# main.net
KiCad netlist of a schematic drawn in EAGLE
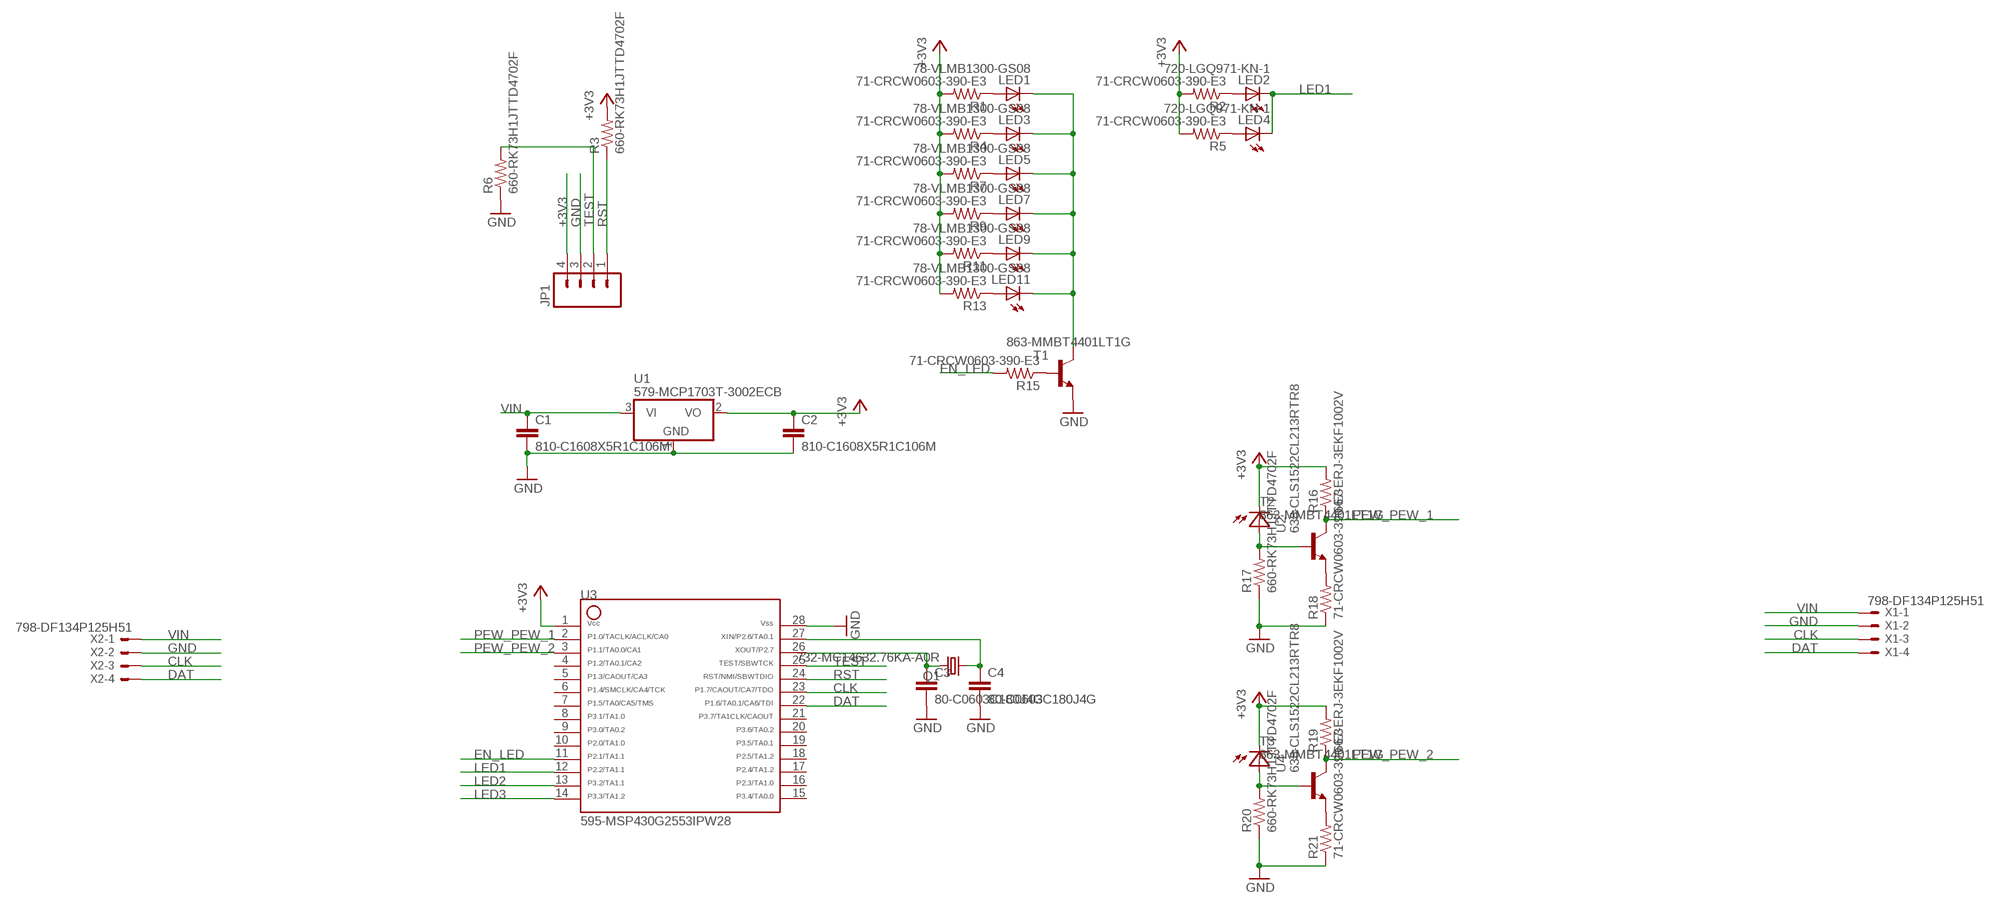
[diagram p0: schematic, sheet 1]

(export (version "E")
  (design (tool "Eeschema 10.0.6"))
  (components
    (comp (ref "C1")
      (value "810-C1608X5R1C106M")
      (footprint "eagle-import:0603-CAP")
      (libsource (lib "eagle-import") (part "CAP0603-CAP"))
    )
    (comp (ref "C2")
      (value "810-C1608X5R1C106M")
      (footprint "eagle-import:0603-CAP")
      (libsource (lib "eagle-import") (part "CAP0603-CAP"))
    )
    (comp (ref "C3")
      (value "80-C0603C180J4G")
      (footprint "eagle-import:0603-CAP")
      (libsource (lib "eagle-import") (part "CAP0603-CAP"))
    )
    (comp (ref "C4")
      (value "80-C0603C180J4G")
      (footprint "eagle-import:0603-CAP")
      (libsource (lib "eagle-import") (part "CAP0603-CAP"))
    )
    (comp (ref "JP1")
      (value "M04PTH")
      (footprint "eagle-import:1X04")
      (libsource (lib "eagle-import") (part "M04PTH"))
    )
    (comp (ref "LED1")
      (value "78-VLMB1300-GS08")
      (footprint "eagle-import:LED-0603")
      (libsource (lib "eagle-import") (part "LED0603"))
    )
    (comp (ref "LED2")
      (value "720-LGQ971-KN-1")
      (footprint "eagle-import:LED-0603")
      (libsource (lib "eagle-import") (part "LED0603"))
    )
    (comp (ref "LED3")
      (value "78-VLMB1300-GS08")
      (footprint "eagle-import:LED-0603")
      (libsource (lib "eagle-import") (part "LED0603"))
    )
    (comp (ref "LED4")
      (value "720-LGQ971-KN-1")
      (footprint "eagle-import:LED-0603")
      (libsource (lib "eagle-import") (part "LED0603"))
    )
    (comp (ref "LED5")
      (value "78-VLMB1300-GS08")
      (footprint "eagle-import:LED-0603")
      (libsource (lib "eagle-import") (part "LED0603"))
    )
    (comp (ref "LED7")
      (value "78-VLMB1300-GS08")
      (footprint "eagle-import:LED-0603")
      (libsource (lib "eagle-import") (part "LED0603"))
    )
    (comp (ref "LED9")
      (value "78-VLMB1300-GS08")
      (footprint "eagle-import:LED-0603")
      (libsource (lib "eagle-import") (part "LED0603"))
    )
    (comp (ref "LED11")
      (value "78-VLMB1300-GS08")
      (footprint "eagle-import:LED-0603")
      (libsource (lib "eagle-import") (part "LED0603"))
    )
    (comp (ref "Q1")
      (value "732-MC14632.76KA-A0R")
      (footprint "eagle-import:CRYSTAL-32KHZ-SMD_EPSON_MC146")
      (libsource (lib "eagle-import") (part "CRYSTALEPSONMC146"))
    )
    (comp (ref "R1")
      (value "71-CRCW0603-390-E3")
      (footprint "eagle-import:R0603")
      (libsource (lib "eagle-import") (part "R-US_R0603"))
    )
    (comp (ref "R2")
      (value "71-CRCW0603-390-E3")
      (footprint "eagle-import:R0603")
      (libsource (lib "eagle-import") (part "R-US_R0603"))
    )
    (comp (ref "R3")
      (value "660-RK73H1JTTD4702F")
      (footprint "eagle-import:R0603")
      (libsource (lib "eagle-import") (part "R-US_R0603"))
    )
    (comp (ref "R4")
      (value "71-CRCW0603-390-E3")
      (footprint "eagle-import:R0603")
      (libsource (lib "eagle-import") (part "R-US_R0603"))
    )
    (comp (ref "R5")
      (value "71-CRCW0603-390-E3")
      (footprint "eagle-import:R0603")
      (libsource (lib "eagle-import") (part "R-US_R0603"))
    )
    (comp (ref "R6")
      (value "660-RK73H1JTTD4702F")
      (footprint "eagle-import:R0603")
      (libsource (lib "eagle-import") (part "R-US_R0603"))
    )
    (comp (ref "R7")
      (value "71-CRCW0603-390-E3")
      (footprint "eagle-import:R0603")
      (libsource (lib "eagle-import") (part "R-US_R0603"))
    )
    (comp (ref "R9")
      (value "71-CRCW0603-390-E3")
      (footprint "eagle-import:R0603")
      (libsource (lib "eagle-import") (part "R-US_R0603"))
    )
    (comp (ref "R11")
      (value "71-CRCW0603-390-E3")
      (footprint "eagle-import:R0603")
      (libsource (lib "eagle-import") (part "R-US_R0603"))
    )
    (comp (ref "R13")
      (value "71-CRCW0603-390-E3")
      (footprint "eagle-import:R0603")
      (libsource (lib "eagle-import") (part "R-US_R0603"))
    )
    (comp (ref "R15")
      (value "71-CRCW0603-390-E3")
      (footprint "eagle-import:R0603")
      (libsource (lib "eagle-import") (part "R-US_R0603"))
    )
    (comp (ref "R16")
      (value "667-ERJ-3EKF1002V")
      (footprint "eagle-import:R0603")
      (libsource (lib "eagle-import") (part "R-US_R0603"))
    )
    (comp (ref "R17")
      (value "660-RK73H1JTTD4702F")
      (footprint "eagle-import:R0603")
      (libsource (lib "eagle-import") (part "R-US_R0603"))
    )
    (comp (ref "R18")
      (value "71-CRCW0603-390-E3")
      (footprint "eagle-import:R0603")
      (libsource (lib "eagle-import") (part "R-US_R0603"))
    )
    (comp (ref "R19")
      (value "667-ERJ-3EKF1002V")
      (footprint "eagle-import:R0603")
      (libsource (lib "eagle-import") (part "R-US_R0603"))
    )
    (comp (ref "R20")
      (value "660-RK73H1JTTD4702F")
      (footprint "eagle-import:R0603")
      (libsource (lib "eagle-import") (part "R-US_R0603"))
    )
    (comp (ref "R21")
      (value "71-CRCW0603-390-E3")
      (footprint "eagle-import:R0603")
      (libsource (lib "eagle-import") (part "R-US_R0603"))
    )
    (comp (ref "T1")
      (value "863-MMBT4401LT1G")
      (footprint "eagle-import:SOT23-BEC")
      (libsource (lib "eagle-import") (part "-NPN-SOT23-BECMMBT4401LT1"))
    )
    (comp (ref "T2")
      (value "863-MMBT4401LT1G")
      (footprint "eagle-import:SOT23-BEC")
      (libsource (lib "eagle-import") (part "-NPN-SOT23-BECMMBT4401LT1"))
    )
    (comp (ref "T3")
      (value "863-MMBT4401LT1G")
      (footprint "eagle-import:SOT23-BEC")
      (libsource (lib "eagle-import") (part "-NPN-SOT23-BECMMBT4401LT1"))
    )
    (comp (ref "U1")
      (value "579-MCP1703T-3002ECB")
      (footprint "eagle-import:SOT23")
      (libsource (lib "eagle-import") (part "MCP1703CB"))
    )
    (comp (ref "U2")
      (value "638-CLS1522CL213RTR8")
      (footprint "eagle-import:CLS15")
      (libsource (lib "eagle-import") (part "CLS15CLS15"))
    )
    (comp (ref "U3")
      (value "595-MSP430G2553IPW28")
      (footprint "eagle-import:PW28")
      (libsource (lib "eagle-import") (part "MSP430G2553"))
    )
    (comp (ref "U4")
      (value "638-CLS1522CL213RTR8")
      (footprint "eagle-import:CLS15")
      (libsource (lib "eagle-import") (part "CLS15CLS15"))
    )
    (comp (ref "X1")
      (value "798-DF134P125H51")
      (footprint "eagle-import:53261-04")
      (libsource (lib "eagle-import") (part "53?-04261"))
    )
    (comp (ref "X2")
      (value "798-DF134P125H51")
      (footprint "eagle-import:53261-04")
      (libsource (lib "eagle-import") (part "53?-04261"))
    )
  )
  (nets
    (net (code "1") (name "+3V3") (class "Default")
      (node (ref "C2") (pin "1") (pinfunction "1_1") (pintype "passive"))
      (node (ref "JP1") (pin "4") (pinfunction "4_4") (pintype "passive"))
      (node (ref "R1") (pin "2") (pinfunction "2_2") (pintype "passive"))
      (node (ref "R11") (pin "2") (pinfunction "2_2") (pintype "passive"))
      (node (ref "R13") (pin "2") (pinfunction "2_2") (pintype "passive"))
      (node (ref "R16") (pin "2") (pinfunction "2_2") (pintype "passive"))
      (node (ref "R19") (pin "2") (pinfunction "2_2") (pintype "passive"))
      (node (ref "R2") (pin "2") (pinfunction "2_2") (pintype "passive"))
      (node (ref "R3") (pin "2") (pinfunction "2_2") (pintype "passive"))
      (node (ref "R4") (pin "2") (pinfunction "2_2") (pintype "passive"))
      (node (ref "R5") (pin "2") (pinfunction "2_2") (pintype "passive"))
      (node (ref "R7") (pin "2") (pinfunction "2_2") (pintype "passive"))
      (node (ref "R9") (pin "2") (pinfunction "2_2") (pintype "passive"))
      (node (ref "U1") (pin "2") (pinfunction "VO_2") (pintype "passive"))
      (node (ref "U2") (pin "3") (pinfunction "C_3") (pintype "passive"))
      (node (ref "U2") (pin "4") (pinfunction "C_4") (pintype "passive"))
      (node (ref "U3") (pin "1") (pinfunction "1_1") (pintype "power_in"))
      (node (ref "U4") (pin "3") (pinfunction "C_3") (pintype "passive"))
      (node (ref "U4") (pin "4") (pinfunction "C_4") (pintype "passive"))
    )
    (net (code "2") (name "/CLK") (class "Default")
      (node (ref "U3") (pin "23") (pinfunction "23_23") (pintype "bidirectional"))
      (node (ref "X1") (pin "3") (pinfunction "S_3") (pintype "passive"))
      (node (ref "X2") (pin "3") (pinfunction "S_3") (pintype "passive"))
    )
    (net (code "3") (name "/DAT") (class "Default")
      (node (ref "U3") (pin "22") (pinfunction "22_22") (pintype "bidirectional"))
      (node (ref "X1") (pin "4") (pinfunction "S_4") (pintype "passive"))
      (node (ref "X2") (pin "4") (pinfunction "S_4") (pintype "passive"))
    )
    (net (code "4") (name "/EN_LED") (class "Default")
      (node (ref "R15") (pin "2") (pinfunction "2_2") (pintype "passive"))
      (node (ref "U3") (pin "11") (pinfunction "11_11") (pintype "bidirectional"))
    )
    (net (code "5") (name "/LED1") (class "Default")
      (node (ref "LED2") (pin "C") (pinfunction "C_C") (pintype "passive"))
      (node (ref "LED4") (pin "C") (pinfunction "C_C") (pintype "passive"))
      (node (ref "U3") (pin "12") (pinfunction "12_12") (pintype "bidirectional"))
    )
    (net (code "6") (name "/LED2") (class "Default")
      (node (ref "U3") (pin "13") (pinfunction "13_13") (pintype "bidirectional"))
    )
    (net (code "7") (name "/LED3") (class "Default")
      (node (ref "U3") (pin "14") (pinfunction "14_14") (pintype "bidirectional"))
    )
    (net (code "8") (name "/PEW_PEW_1") (class "Default")
      (node (ref "R16") (pin "1") (pinfunction "1_1") (pintype "passive"))
      (node (ref "T2") (pin "C") (pinfunction "C_C") (pintype "passive"))
      (node (ref "U3") (pin "2") (pinfunction "2_2") (pintype "bidirectional"))
    )
    (net (code "9") (name "/PEW_PEW_2") (class "Default")
      (node (ref "R19") (pin "1") (pinfunction "1_1") (pintype "passive"))
      (node (ref "T3") (pin "C") (pinfunction "C_C") (pintype "passive"))
      (node (ref "U3") (pin "3") (pinfunction "3_3") (pintype "bidirectional"))
    )
    (net (code "10") (name "/RST") (class "Default")
      (node (ref "JP1") (pin "1") (pinfunction "1_1") (pintype "passive"))
      (node (ref "R3") (pin "1") (pinfunction "1_1") (pintype "passive"))
      (node (ref "U3") (pin "24") (pinfunction "24_24") (pintype "bidirectional"))
    )
    (net (code "11") (name "/TEST") (class "Default")
      (node (ref "JP1") (pin "2") (pinfunction "2_2") (pintype "passive"))
      (node (ref "R6") (pin "2") (pinfunction "2_2") (pintype "passive"))
      (node (ref "U3") (pin "25") (pinfunction "25_25") (pintype "input"))
    )
    (net (code "12") (name "/VIN") (class "Default")
      (node (ref "C1") (pin "1") (pinfunction "1_1") (pintype "passive"))
      (node (ref "U1") (pin "3") (pinfunction "VI_3") (pintype "input"))
      (node (ref "X1") (pin "1") (pinfunction "S_1") (pintype "passive"))
      (node (ref "X2") (pin "1") (pinfunction "S_1") (pintype "passive"))
    )
    (net (code "13") (name "GND") (class "Default")
      (node (ref "C1") (pin "2") (pinfunction "2_2") (pintype "passive"))
      (node (ref "C2") (pin "2") (pinfunction "2_2") (pintype "passive"))
      (node (ref "C3") (pin "2") (pinfunction "2_2") (pintype "passive"))
      (node (ref "C4") (pin "2") (pinfunction "2_2") (pintype "passive"))
      (node (ref "JP1") (pin "3") (pinfunction "3_3") (pintype "passive"))
      (node (ref "R17") (pin "1") (pinfunction "1_1") (pintype "passive"))
      (node (ref "R18") (pin "1") (pinfunction "1_1") (pintype "passive"))
      (node (ref "R20") (pin "1") (pinfunction "1_1") (pintype "passive"))
      (node (ref "R21") (pin "1") (pinfunction "1_1") (pintype "passive"))
      (node (ref "R6") (pin "1") (pinfunction "1_1") (pintype "passive"))
      (node (ref "T1") (pin "E") (pinfunction "E_E") (pintype "passive"))
      (node (ref "U1") (pin "1") (pinfunction "GND_1") (pintype "passive"))
      (node (ref "U3") (pin "28") (pinfunction "28_28") (pintype "power_in"))
      (node (ref "X1") (pin "2") (pinfunction "S_2") (pintype "passive"))
      (node (ref "X2") (pin "2") (pinfunction "S_2") (pintype "passive"))
    )
    (net (code "14") (name "Net-(LED1-PadA)") (class "Default")
      (node (ref "LED1") (pin "A") (pinfunction "A_A") (pintype "passive"))
      (node (ref "R1") (pin "1") (pinfunction "1_1") (pintype "passive"))
    )
    (net (code "15") (name "Net-(LED1-PadC)") (class "Default")
      (node (ref "LED1") (pin "C") (pinfunction "C_C") (pintype "passive"))
      (node (ref "LED11") (pin "C") (pinfunction "C_C") (pintype "passive"))
      (node (ref "LED3") (pin "C") (pinfunction "C_C") (pintype "passive"))
      (node (ref "LED5") (pin "C") (pinfunction "C_C") (pintype "passive"))
      (node (ref "LED7") (pin "C") (pinfunction "C_C") (pintype "passive"))
      (node (ref "LED9") (pin "C") (pinfunction "C_C") (pintype "passive"))
      (node (ref "T1") (pin "C") (pinfunction "C_C") (pintype "passive"))
    )
    (net (code "16") (name "Net-(LED2-PadA)") (class "Default")
      (node (ref "LED2") (pin "A") (pinfunction "A_A") (pintype "passive"))
      (node (ref "R2") (pin "1") (pinfunction "1_1") (pintype "passive"))
    )
    (net (code "17") (name "Net-(LED3-PadA)") (class "Default")
      (node (ref "LED3") (pin "A") (pinfunction "A_A") (pintype "passive"))
      (node (ref "R4") (pin "1") (pinfunction "1_1") (pintype "passive"))
    )
    (net (code "18") (name "Net-(LED4-PadA)") (class "Default")
      (node (ref "LED4") (pin "A") (pinfunction "A_A") (pintype "passive"))
      (node (ref "R5") (pin "1") (pinfunction "1_1") (pintype "passive"))
    )
    (net (code "19") (name "Net-(LED5-PadA)") (class "Default")
      (node (ref "LED5") (pin "A") (pinfunction "A_A") (pintype "passive"))
      (node (ref "R7") (pin "1") (pinfunction "1_1") (pintype "passive"))
    )
    (net (code "20") (name "Net-(LED7-PadA)") (class "Default")
      (node (ref "LED7") (pin "A") (pinfunction "A_A") (pintype "passive"))
      (node (ref "R9") (pin "1") (pinfunction "1_1") (pintype "passive"))
    )
    (net (code "21") (name "Net-(LED9-PadA)") (class "Default")
      (node (ref "LED9") (pin "A") (pinfunction "A_A") (pintype "passive"))
      (node (ref "R11") (pin "1") (pinfunction "1_1") (pintype "passive"))
    )
    (net (code "22") (name "Net-(LED11-PadA)") (class "Default")
      (node (ref "LED11") (pin "A") (pinfunction "A_A") (pintype "passive"))
      (node (ref "R13") (pin "1") (pinfunction "1_1") (pintype "passive"))
    )
    (net (code "23") (name "Net-(Q1-1)") (class "Default")
      (node (ref "C4") (pin "1") (pinfunction "1_1") (pintype "passive"))
      (node (ref "Q1") (pin "P$2") (pinfunction "1_P$2") (pintype "passive"))
      (node (ref "U3") (pin "27") (pinfunction "27_27") (pintype "bidirectional"))
    )
    (net (code "24") (name "Net-(Q1-2)") (class "Default")
      (node (ref "C3") (pin "1") (pinfunction "1_1") (pintype "passive"))
      (node (ref "Q1") (pin "P$1") (pinfunction "2_P$1") (pintype "passive"))
      (node (ref "U3") (pin "26") (pinfunction "26_26") (pintype "bidirectional"))
    )
    (net (code "25") (name "Net-(R15-Pad1)") (class "Default")
      (node (ref "R15") (pin "1") (pinfunction "1_1") (pintype "passive"))
      (node (ref "T1") (pin "B") (pinfunction "B_B") (pintype "passive"))
    )
    (net (code "26") (name "Net-(R17-Pad2)") (class "Default")
      (node (ref "R17") (pin "2") (pinfunction "2_2") (pintype "passive"))
      (node (ref "T2") (pin "B") (pinfunction "B_B") (pintype "passive"))
      (node (ref "U2") (pin "1") (pinfunction "A_1") (pintype "passive"))
      (node (ref "U2") (pin "2") (pinfunction "A_2") (pintype "passive"))
    )
    (net (code "27") (name "Net-(R18-Pad2)") (class "Default")
      (node (ref "R18") (pin "2") (pinfunction "2_2") (pintype "passive"))
      (node (ref "T2") (pin "E") (pinfunction "E_E") (pintype "passive"))
    )
    (net (code "28") (name "Net-(R20-Pad2)") (class "Default")
      (node (ref "R20") (pin "2") (pinfunction "2_2") (pintype "passive"))
      (node (ref "T3") (pin "B") (pinfunction "B_B") (pintype "passive"))
      (node (ref "U4") (pin "1") (pinfunction "A_1") (pintype "passive"))
      (node (ref "U4") (pin "2") (pinfunction "A_2") (pintype "passive"))
    )
    (net (code "29") (name "Net-(R21-Pad2)") (class "Default")
      (node (ref "R21") (pin "2") (pinfunction "2_2") (pintype "passive"))
      (node (ref "T3") (pin "E") (pinfunction "E_E") (pintype "passive"))
    )
    (net (code "30") (name "unconnected-(U3-Pad4)") (class "Default")
      (node (ref "U3") (pin "4") (pinfunction "4_4") (pintype "bidirectional"))
    )
    (net (code "31") (name "unconnected-(U3-Pad5)") (class "Default")
      (node (ref "U3") (pin "5") (pinfunction "5_5") (pintype "bidirectional"))
    )
    (net (code "32") (name "unconnected-(U3-Pad6)") (class "Default")
      (node (ref "U3") (pin "6") (pinfunction "6_6") (pintype "bidirectional"))
    )
    (net (code "33") (name "unconnected-(U3-Pad7)") (class "Default")
      (node (ref "U3") (pin "7") (pinfunction "7_7") (pintype "bidirectional"))
    )
    (net (code "34") (name "unconnected-(U3-Pad8)") (class "Default")
      (node (ref "U3") (pin "8") (pinfunction "8_8") (pintype "bidirectional"))
    )
    (net (code "35") (name "unconnected-(U3-Pad9)") (class "Default")
      (node (ref "U3") (pin "9") (pinfunction "9_9") (pintype "bidirectional"))
    )
    (net (code "36") (name "unconnected-(U3-Pad10)") (class "Default")
      (node (ref "U3") (pin "10") (pinfunction "10_10") (pintype "bidirectional"))
    )
    (net (code "37") (name "unconnected-(U3-Pad15)") (class "Default")
      (node (ref "U3") (pin "15") (pinfunction "15_15") (pintype "bidirectional"))
    )
    (net (code "38") (name "unconnected-(U3-Pad16)") (class "Default")
      (node (ref "U3") (pin "16") (pinfunction "16_16") (pintype "bidirectional"))
    )
    (net (code "39") (name "unconnected-(U3-Pad17)") (class "Default")
      (node (ref "U3") (pin "17") (pinfunction "17_17") (pintype "bidirectional"))
    )
    (net (code "40") (name "unconnected-(U3-Pad18)") (class "Default")
      (node (ref "U3") (pin "18") (pinfunction "18_18") (pintype "bidirectional"))
    )
    (net (code "41") (name "unconnected-(U3-Pad19)") (class "Default")
      (node (ref "U3") (pin "19") (pinfunction "19_19") (pintype "bidirectional"))
    )
    (net (code "42") (name "unconnected-(U3-Pad20)") (class "Default")
      (node (ref "U3") (pin "20") (pinfunction "20_20") (pintype "bidirectional"))
    )
    (net (code "43") (name "unconnected-(U3-Pad21)") (class "Default")
      (node (ref "U3") (pin "21") (pinfunction "21_21") (pintype "bidirectional"))
    )
  )
)
